# WAFC.net
KiCad netlist of a schematic drawn in Altium Designer
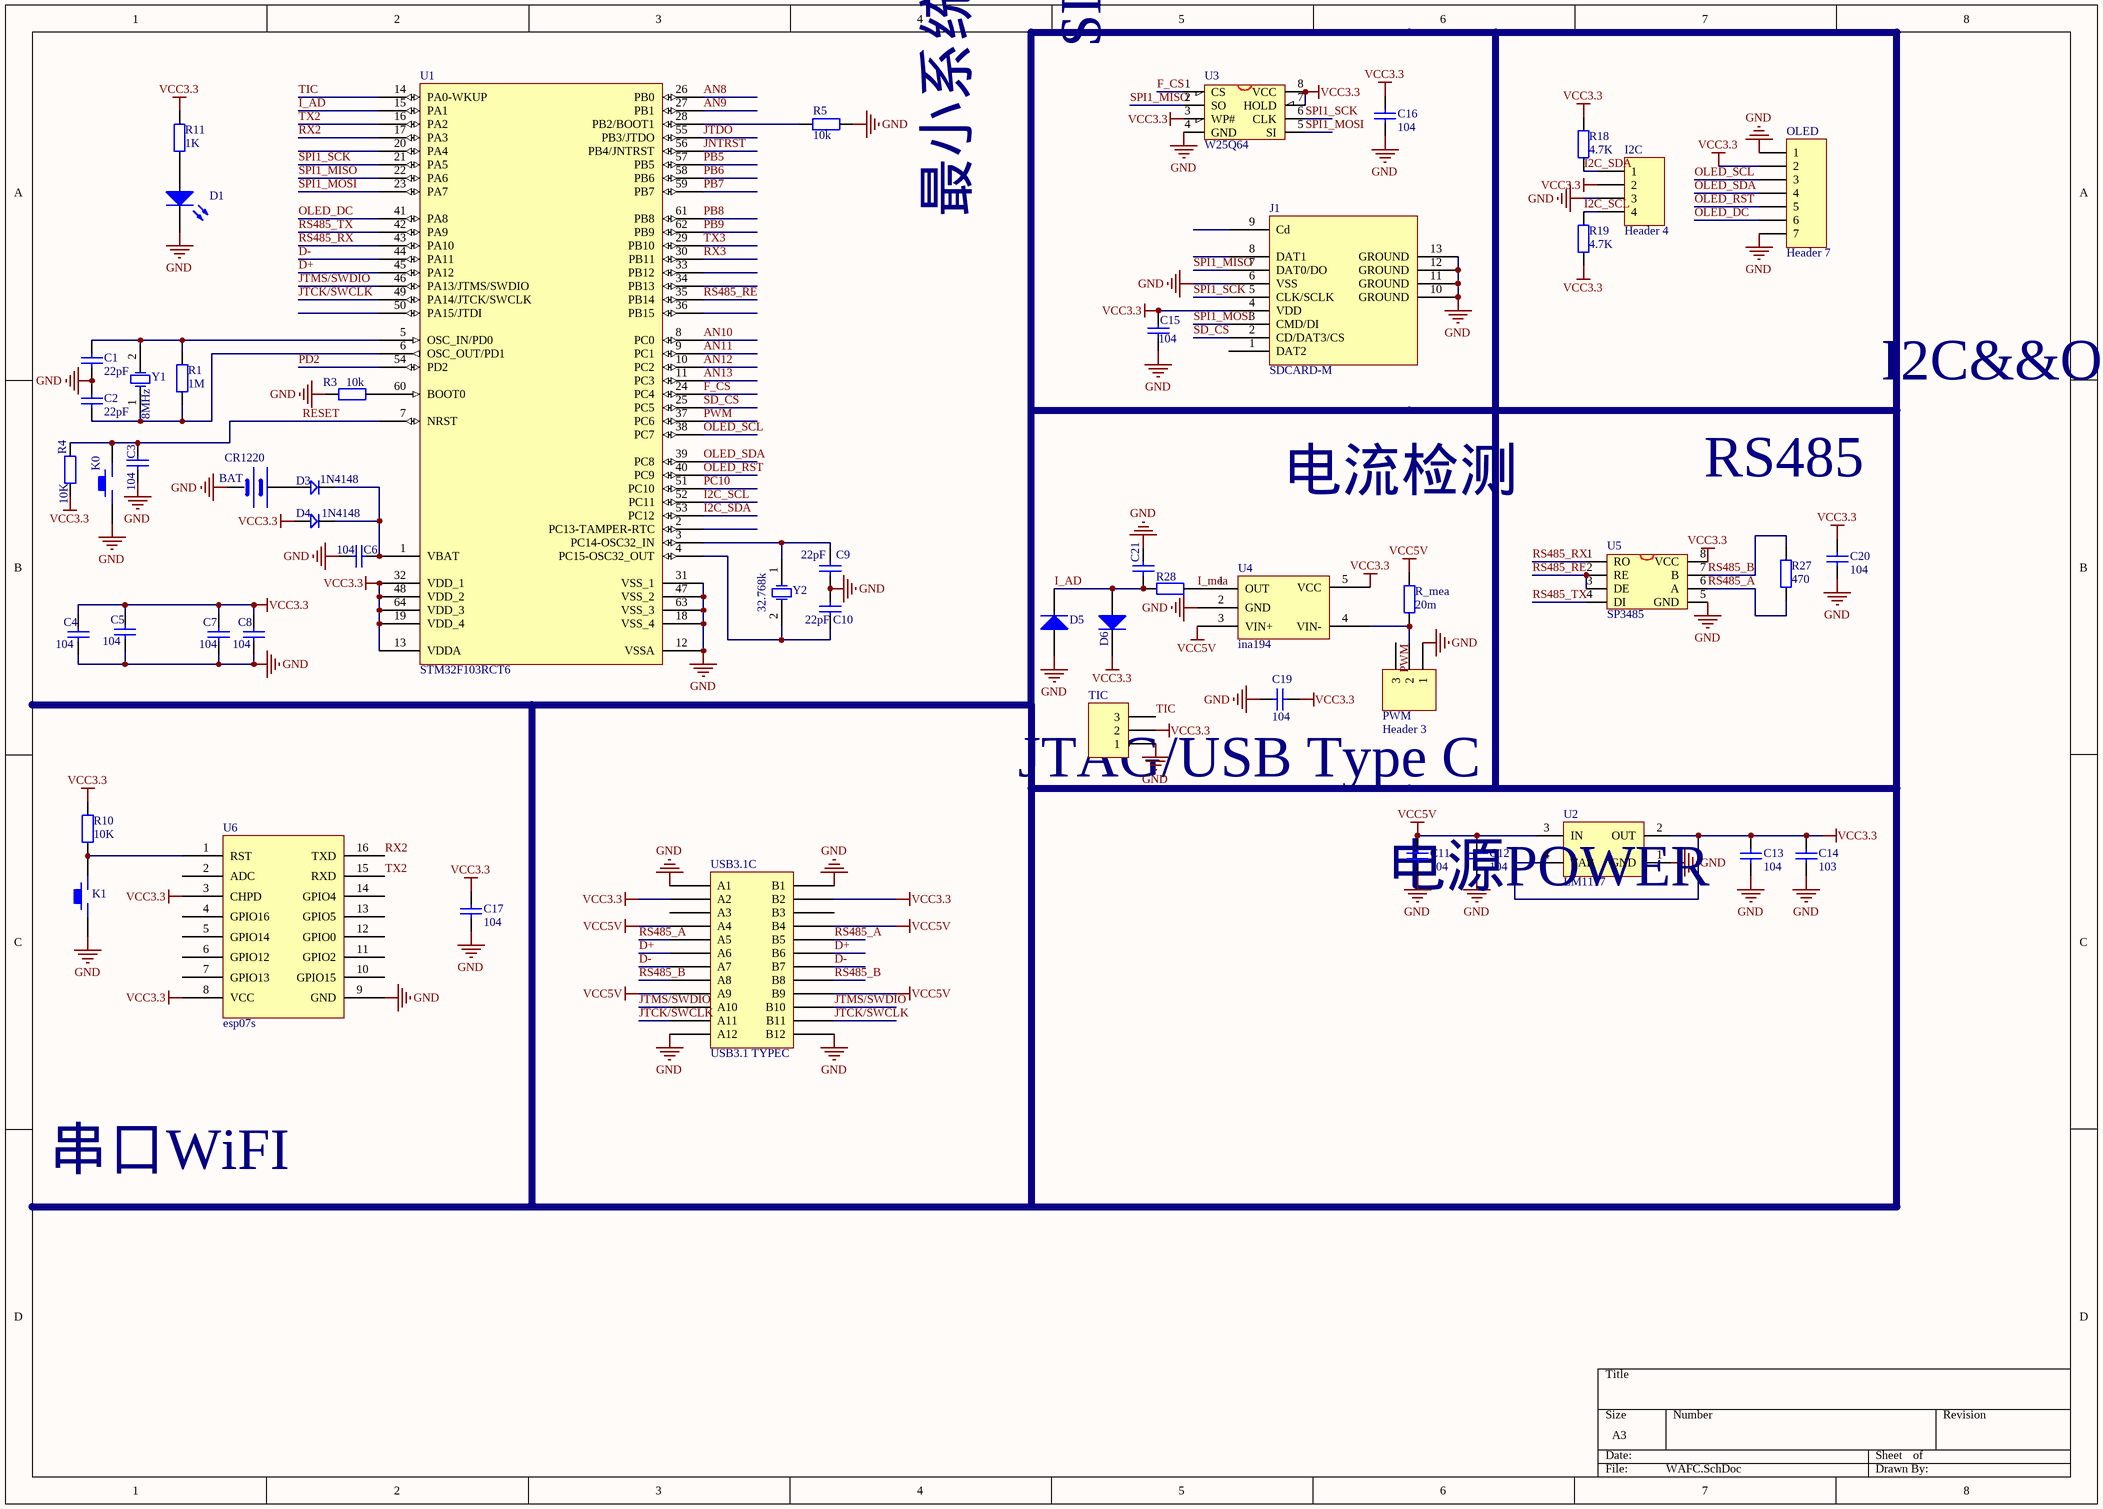
[diagram p0: WAFC.SchDoc]

(export (version "E")
  (design (tool "Eeschema 10.0.6"))
  (components
    (comp (ref "BAT") (value "CR1220") (footprint "BATM") (libsource (lib "WARSHIP") (part "BAT")))
    (comp (ref "C1")
      (value "22pF")
      (footprint "0603")
      (description "Capacitor")
      (fields (field (name "Comment") "Cap") (field (name "PUBLISHER") "Altium Limited"))
      (libsource (lib "Miscellaneous Devices") (part "Cap"))
    )
    (comp (ref "C2")
      (value "22pF")
      (footprint "0603")
      (description "Capacitor")
      (fields (field (name "Comment") "Cap") (field (name "PUBLISHER") "Altium Limited"))
      (libsource (lib "Miscellaneous Devices") (part "Cap"))
    )
    (comp (ref "C3")
      (value "104")
      (footprint "0603")
      (description "Capacitor")
      (fields (field (name "Comment") "Cap") (field (name "PUBLISHER") "Altium Limited"))
      (libsource (lib "Miscellaneous Devices") (part "Cap"))
    )
    (comp (ref "C4")
      (value "104")
      (footprint "0603")
      (description "Capacitor")
      (fields (field (name "Comment") "Cap") (field (name "PUBLISHER") "Altium Limited"))
      (libsource (lib "Miscellaneous Devices") (part "Cap"))
    )
    (comp (ref "C5")
      (value "104")
      (footprint "0603")
      (description "Capacitor")
      (fields (field (name "Comment") "Cap") (field (name "PUBLISHER") "Altium Limited"))
      (libsource (lib "Miscellaneous Devices") (part "Cap"))
    )
    (comp (ref "C6")
      (value "104")
      (footprint "0603")
      (description "Capacitor")
      (fields (field (name "Comment") "Cap") (field (name "PUBLISHER") "Altium Limited"))
      (libsource (lib "Miscellaneous Devices") (part "Cap"))
    )
    (comp (ref "C7")
      (value "104")
      (footprint "0603")
      (description "Capacitor")
      (fields (field (name "Comment") "Cap") (field (name "PUBLISHER") "Altium Limited"))
      (libsource (lib "Miscellaneous Devices") (part "Cap"))
    )
    (comp (ref "C8")
      (value "104")
      (footprint "0603")
      (description "Capacitor")
      (fields (field (name "Comment") "Cap") (field (name "PUBLISHER") "Altium Limited"))
      (libsource (lib "Miscellaneous Devices") (part "Cap"))
    )
    (comp (ref "C9")
      (value "22pF")
      (footprint "0603")
      (description "Capacitor")
      (fields (field (name "Comment") "Cap") (field (name "PUBLISHER") "Altium Limited"))
      (libsource (lib "Miscellaneous Devices") (part "Cap"))
    )
    (comp (ref "C10")
      (value "22pF")
      (footprint "0603")
      (description "Capacitor")
      (fields (field (name "Comment") "Cap") (field (name "PUBLISHER") "Altium Limited"))
      (libsource (lib "Miscellaneous Devices") (part "Cap"))
    )
    (comp (ref "C11")
      (value "104")
      (footprint "0603")
      (description "Capacitor")
      (fields (field (name "Comment") "Cap") (field (name "PUBLISHER") "Altium Limited"))
      (libsource (lib "Miscellaneous Devices") (part "Cap"))
    )
    (comp (ref "C12")
      (value "104")
      (footprint "0603")
      (description "Capacitor")
      (fields (field (name "Comment") "Cap") (field (name "PUBLISHER") "Altium Limited"))
      (libsource (lib "Miscellaneous Devices") (part "Cap"))
    )
    (comp (ref "C13")
      (value "104")
      (footprint "0603")
      (description "Capacitor")
      (fields (field (name "Comment") "Cap") (field (name "PUBLISHER") "Altium Limited"))
      (libsource (lib "Miscellaneous Devices") (part "Cap"))
    )
    (comp (ref "C14")
      (value "103")
      (footprint "0603")
      (description "Capacitor")
      (fields (field (name "Comment") "Cap") (field (name "PUBLISHER") "Altium Limited"))
      (libsource (lib "Miscellaneous Devices") (part "Cap"))
    )
    (comp (ref "C15")
      (value "104")
      (footprint "0603")
      (description "Capacitor")
      (fields (field (name "Comment") "Cap") (field (name "PUBLISHER") "Altium Limited"))
      (libsource (lib "Miscellaneous Devices") (part "Cap"))
    )
    (comp (ref "C16")
      (value "104")
      (footprint "0603")
      (description "Capacitor")
      (fields (field (name "Comment") "Cap") (field (name "PUBLISHER") "Altium Limited"))
      (libsource (lib "Miscellaneous Devices") (part "Cap"))
    )
    (comp (ref "C17")
      (value "104")
      (footprint "0603")
      (description "Capacitor")
      (fields (field (name "Comment") "Cap") (field (name "PUBLISHER") "Altium Limited"))
      (libsource (lib "Miscellaneous Devices") (part "Cap"))
    )
    (comp (ref "C19")
      (value "104")
      (footprint "0603")
      (description "Capacitor")
      (fields (field (name "Comment") "Cap") (field (name "PUBLISHER") "Altium Limited"))
      (libsource (lib "Miscellaneous Devices") (part "Cap"))
    )
    (comp (ref "C20")
      (value "104")
      (footprint "0603")
      (description "Capacitor")
      (fields (field (name "Comment") "Cap") (field (name "PUBLISHER") "Altium Limited"))
      (libsource (lib "Miscellaneous Devices") (part "Cap"))
    )
    (comp (ref "C21")
      (value "Cap")
      (footprint "0603")
      (description "Capacitor")
      (fields (field (name "PUBLISHER") "Altium Limited"))
      (libsource (lib "Miscellaneous Devices") (part "Cap"))
    )
    (comp (ref "D1")
      (value "LED2")
      (footprint "0603")
      (description "Typical RED, GREEN, YELLOW, AMBER GaAs LED")
      (fields (field (name "PUBLISHER") "Altium Limited"))
      (libsource (lib "Miscellaneous Devices") (part "LED2"))
    )
    (comp (ref "D3") (value "1N4148") (footprint "DIODE_SOP") (libsource (lib "WARSHIP") (part "D")))
    (comp (ref "D4") (value "1N4148") (footprint "DIODE_SOP") (libsource (lib "WARSHIP") (part "D")))
    (comp (ref "D5")
      (value "SS14")
      (footprint "IN5819")
      (description "1 Amp General Purpose Rectifier")
      (fields (field (name "PUBLISHER") "Altium Limited"))
      (libsource (lib "Miscellaneous Devices") (part "Diode 1N4007"))
    )
    (comp (ref "D6")
      (value "SS14")
      (footprint "IN5819")
      (description "1 Amp General Purpose Rectifier")
      (fields (field (name "PUBLISHER") "Altium Limited"))
      (libsource (lib "Miscellaneous Devices") (part "Diode 1N4007"))
    )
    (comp (ref "I2C")
      (value "Header 4")
      (footprint "4P")
      (description "Header, 4-Pin")
      (fields (field (name "PUBLISHER") "Altium Limited"))
      (libsource (lib "Miscellaneous Connectors") (part "Header 4"))
    )
    (comp (ref "J1")
      (value "SDCARD-M")
      (footprint "SDCARD-M")
      (description "TF卡槽")
      (libsource (lib "MYLIB") (part "SDCARD-M"))
    )
    (comp (ref "K0") (value "K1") (footprint "sop2") (libsource (lib "MYLIB") (part "KEY")))
    (comp (ref "K1") (value "K3") (footprint "sop2") (libsource (lib "MYLIB") (part "KEY")))
    (comp (ref "OLED")
      (value "Header 7")
      (footprint "HDR1X7")
      (description "Header, 7-Pin")
      (fields (field (name "PUBLISHER") "Altium Limited"))
      (libsource (lib "Miscellaneous Connectors") (part "Header 7"))
    )
    (comp (ref "PWM")
      (value "Header 3")
      (footprint "HDR1X3")
      (description "Header, 3-Pin")
      (fields (field (name "PUBLISHER") "Altium Limited"))
      (libsource (lib "") (part "Header 3_1"))
    )
    (comp (ref "R1")
      (value "1M")
      (footprint "0603")
      (description "Resistor")
      (fields (field (name "Comment") "Res2") (field (name "PUBLISHER") "Altium Limited"))
      (libsource (lib "") (part "Res2_1"))
    )
    (comp (ref "R3")
      (value "10k")
      (footprint "0603")
      (description "Resistor")
      (fields (field (name "Comment") "Res2") (field (name "PUBLISHER") "Altium Limited"))
      (libsource (lib "") (part "Res2_2"))
    )
    (comp (ref "R4")
      (value "10K")
      (footprint "0603")
      (description "Resistor")
      (fields (field (name "Comment") "Res2") (field (name "PUBLISHER") "Altium Limited"))
      (libsource (lib "") (part "Res2_1"))
    )
    (comp (ref "R5")
      (value "10k")
      (footprint "0603")
      (description "Resistor")
      (fields (field (name "Comment") "Res2") (field (name "PUBLISHER") "Altium Limited"))
      (libsource (lib "") (part "Res2_2"))
    )
    (comp (ref "R10")
      (value "10K")
      (footprint "0603")
      (description "Resistor")
      (fields (field (name "Comment") "Res2") (field (name "PUBLISHER") "Altium Limited"))
      (libsource (lib "Miscellaneous Devices") (part "Res2"))
    )
    (comp (ref "R11")
      (value "1K")
      (footprint "0603")
      (description "Resistor")
      (fields (field (name "Comment") "Res2") (field (name "PUBLISHER") "Altium Limited"))
      (libsource (lib "") (part "Res2_1"))
    )
    (comp (ref "R18")
      (value "4.7K")
      (footprint "0603")
      (description "Resistor")
      (fields (field (name "Comment") "Res2") (field (name "PUBLISHER") "Altium Limited"))
      (libsource (lib "Miscellaneous Devices") (part "Res2"))
    )
    (comp (ref "R19")
      (value "4.7K")
      (footprint "0603")
      (description "Resistor")
      (fields (field (name "Comment") "Res2") (field (name "PUBLISHER") "Altium Limited"))
      (libsource (lib "Miscellaneous Devices") (part "Res2"))
    )
    (comp (ref "R27")
      (value "470")
      (footprint "0603")
      (description "Resistor")
      (fields (field (name "Comment") "Res2") (field (name "PUBLISHER") "Altium Limited"))
      (libsource (lib "Miscellaneous Devices") (part "Res2"))
    )
    (comp (ref "R28")
      (value "Res2")
      (footprint "0603")
      (description "Resistor")
      (fields (field (name "PUBLISHER") "Altium Limited"))
      (libsource (lib "") (part "Res2_3"))
    )
    (comp (ref "R_mea")
      (value "20m")
      (footprint "0805")
      (description "Resistor")
      (fields (field (name "Comment") "Res2") (field (name "PUBLISHER") "Altium Limited"))
      (libsource (lib "") (part "Res2_1"))
    )
    (comp (ref "TIC")
      (value "Header 3")
      (footprint "HDR1X3")
      (description "Header, 3-Pin")
      (fields (field (name "PUBLISHER") "Altium Limited"))
      (libsource (lib "Miscellaneous Connectors") (part "Header 3"))
    )
    (comp (ref "U1")
      (value "STM32F103RCT6")
      (footprint "LQFP64")
      (description "STM32 ARM-based 32-bit MCU with 128 Kbytes Flash, 64-pin LQFP, Industrial Temperature")
      (fields (field (name "PUBLISHER") "Altium Limited"))
      (libsource (lib "MYLIB") (part "STM32F103RBT6"))
    )
    (comp (ref "U2")
      (value "LM1117")
      (footprint "MP04A_N")
      (description "800mA LDO")
      (fields
        (field (name "PARTNUMBER") "LM1117IMP-5.0")
        (field (name "MANUFACTURER") "National Semiconductor")
        (field (name "PUBLISHER") "Altium Limited")
      )
      (libsource (lib "MYLIB") (part "LM1117"))
    )
    (comp (ref "U3")
      (value "W25Q64")
      (footprint "SOIC-8")
      (description "W25X16;SST25VF016;MX25L1605")
      (libsource (lib "WARSHIP") (part "W25X16"))
    )
    (comp (ref "U4") (value "ina194") (footprint "ina194") (libsource (lib "MYLIB") (part "ina194")))
    (comp (ref "U5") (value "SP3485") (footprint "SOP-8") (libsource (lib "WARSHIP") (part "MAX3485")))
    (comp (ref "U6") (value "esp07s") (footprint "ESP07S") (libsource (lib "MYLIB") (part "esp07s")))
    (comp (ref "USB3.1C")
      (value "USB3.1 TYPEC")
      (footprint "MicroUSB TypeC 3.1 - duplicate")
      (libsource (lib "MYLIB") (part "USB3.1 TYPEc"))
    )
    (comp (ref "Y1")
      (value "8MHz")
      (footprint "XTAL_US")
      (description "Crystal Oscillator")
      (fields (field (name "PUBLISHER") "Altium Limited"))
      (libsource (lib "WARSHIP") (part "XTAL"))
    )
    (comp (ref "Y2")
      (value "32.768k")
      (footprint "XTAL32768")
      (description "Crystal Oscillator")
      (fields (field (name "PUBLISHER") "Altium Limited"))
      (libsource (lib "Miscellaneous Devices") (part "XTAL"))
    )
  )
  (nets
    (net (code "1") (name "/AN8") (class "Default")
      (node (ref "U1") (pin "26") (pinfunction "PB0_26") (pintype "bidirectional"))
    )
    (net (code "2") (name "/AN9") (class "Default")
      (node (ref "U1") (pin "27") (pinfunction "PB1_27") (pintype "bidirectional"))
    )
    (net (code "3") (name "/AN10") (class "Default")
      (node (ref "U1") (pin "8") (pinfunction "PC0_8") (pintype "bidirectional"))
    )
    (net (code "4") (name "/AN11") (class "Default")
      (node (ref "U1") (pin "9") (pinfunction "PC1_9") (pintype "bidirectional"))
    )
    (net (code "5") (name "/AN12") (class "Default")
      (node (ref "U1") (pin "10") (pinfunction "PC2_10") (pintype "bidirectional"))
    )
    (net (code "6") (name "/AN13") (class "Default")
      (node (ref "U1") (pin "11") (pinfunction "PC3_11") (pintype "bidirectional"))
    )
    (net (code "7") (name "/D+") (class "Default")
      (node (ref "U1") (pin "45") (pinfunction "PA12_45") (pintype "bidirectional"))
      (node (ref "USB3.1C") (pin "19") (pinfunction "B6_19") (pintype "passive"))
      (node (ref "USB3.1C") (pin "6") (pinfunction "A6_6") (pintype "passive"))
    )
    (net (code "8") (name "/D-") (class "Default")
      (node (ref "U1") (pin "44") (pinfunction "PA11_44") (pintype "bidirectional"))
      (node (ref "USB3.1C") (pin "18") (pinfunction "B7_18") (pintype "passive"))
      (node (ref "USB3.1C") (pin "7") (pinfunction "A7_7") (pintype "passive"))
    )
    (net (code "9") (name "/F_CS") (class "Default")
      (node (ref "U1") (pin "24") (pinfunction "PC4_24") (pintype "bidirectional"))
      (node (ref "U3") (pin "1") (pinfunction "CS_1") (pintype "passive"))
    )
    (net (code "10") (name "/I2C_SCL") (class "Default")
      (node (ref "I2C") (pin "4") (pinfunction "4_4") (pintype "passive"))
      (node (ref "R19") (pin "1") (pinfunction "1_1") (pintype "passive"))
      (node (ref "U1") (pin "52") (pinfunction "PC11_52") (pintype "bidirectional"))
    )
    (net (code "11") (name "/I2C_SDA") (class "Default")
      (node (ref "I2C") (pin "1") (pinfunction "1_1") (pintype "passive"))
      (node (ref "R18") (pin "2") (pinfunction "2_2") (pintype "passive"))
      (node (ref "U1") (pin "53") (pinfunction "PC12_53") (pintype "bidirectional"))
    )
    (net (code "12") (name "/I_AD") (class "Default")
      (node (ref "C21") (pin "1") (pinfunction "1_1") (pintype "passive"))
      (node (ref "D5") (pin "2") (pinfunction "K_2") (pintype "passive"))
      (node (ref "D6") (pin "1") (pinfunction "A_1") (pintype "passive"))
      (node (ref "R28") (pin "1") (pinfunction "1_1") (pintype "passive"))
      (node (ref "U1") (pin "15") (pinfunction "PA1_15") (pintype "bidirectional"))
    )
    (net (code "13") (name "/I_mea") (class "Default")
      (node (ref "R28") (pin "2") (pinfunction "2_2") (pintype "passive"))
      (node (ref "U4") (pin "1") (pinfunction "OUT_1") (pintype "passive"))
    )
    (net (code "14") (name "/JNTRST") (class "Default")
      (node (ref "U1") (pin "56") (pinfunction "PB4/JNTRST_56") (pintype "bidirectional"))
    )
    (net (code "15") (name "/JTCK{slash}SWCLK") (class "Default")
      (node (ref "U1") (pin "49") (pinfunction "PA14/JTCK/SWCLK_49") (pintype "bidirectional"))
      (node (ref "USB3.1C") (pin "11") (pinfunction "A11_11") (pintype "passive"))
      (node (ref "USB3.1C") (pin "14") (pinfunction "B11_14") (pintype "passive"))
    )
    (net (code "16") (name "/JTDO") (class "Default")
      (node (ref "U1") (pin "55") (pinfunction "PB3/JTDO_55") (pintype "bidirectional"))
    )
    (net (code "17") (name "/JTMS{slash}SWDIO") (class "Default")
      (node (ref "U1") (pin "46") (pinfunction "PA13/JTMS/SWDIO_46") (pintype "bidirectional"))
      (node (ref "USB3.1C") (pin "10") (pinfunction "A10_10") (pintype "passive"))
      (node (ref "USB3.1C") (pin "15") (pinfunction "B10_15") (pintype "passive"))
    )
    (net (code "18") (name "/OLED_DC") (class "Default")
      (node (ref "OLED") (pin "6") (pinfunction "6_6") (pintype "passive"))
      (node (ref "U1") (pin "41") (pinfunction "PA8_41") (pintype "bidirectional"))
    )
    (net (code "19") (name "/OLED_RST") (class "Default")
      (node (ref "OLED") (pin "5") (pinfunction "5_5") (pintype "passive"))
      (node (ref "U1") (pin "40") (pinfunction "PC9_40") (pintype "bidirectional"))
    )
    (net (code "20") (name "/OLED_SCL") (class "Default")
      (node (ref "OLED") (pin "3") (pinfunction "3_3") (pintype "passive"))
      (node (ref "U1") (pin "38") (pinfunction "PC7_38") (pintype "bidirectional"))
    )
    (net (code "21") (name "/OLED_SDA") (class "Default")
      (node (ref "OLED") (pin "4") (pinfunction "4_4") (pintype "passive"))
      (node (ref "U1") (pin "39") (pinfunction "PC8_39") (pintype "bidirectional"))
    )
    (net (code "22") (name "/PB5") (class "Default")
      (node (ref "U1") (pin "57") (pinfunction "PB5_57") (pintype "bidirectional"))
    )
    (net (code "23") (name "/PB6") (class "Default")
      (node (ref "U1") (pin "58") (pinfunction "PB6_58") (pintype "bidirectional"))
    )
    (net (code "24") (name "/PB7") (class "Default")
      (node (ref "U1") (pin "59") (pinfunction "PB7_59") (pintype "bidirectional"))
    )
    (net (code "25") (name "/PB8") (class "Default")
      (node (ref "U1") (pin "61") (pinfunction "PB8_61") (pintype "bidirectional"))
    )
    (net (code "26") (name "/PB9") (class "Default")
      (node (ref "U1") (pin "62") (pinfunction "PB9_62") (pintype "bidirectional"))
    )
    (net (code "27") (name "/PC10") (class "Default")
      (node (ref "U1") (pin "51") (pinfunction "PC10_51") (pintype "bidirectional"))
    )
    (net (code "28") (name "/PD2") (class "Default")
      (node (ref "U1") (pin "54") (pinfunction "PD2_54") (pintype "bidirectional"))
    )
    (net (code "29") (name "/PWM") (class "Default")
      (node (ref "PWM") (pin "3") (pinfunction "3_3") (pintype "passive"))
      (node (ref "U1") (pin "37") (pinfunction "PC6_37") (pintype "bidirectional"))
    )
    (net (code "30") (name "/RESET") (class "Default")
      (node (ref "C3") (pin "2") (pinfunction "2_2") (pintype "passive"))
      (node (ref "K0") (pin "2") (pinfunction "2_2") (pintype "passive"))
      (node (ref "R4") (pin "2") (pinfunction "2_2") (pintype "passive"))
      (node (ref "U1") (pin "7") (pinfunction "NRST_7") (pintype "bidirectional"))
    )
    (net (code "31") (name "/RS485_A") (class "Default")
      (node (ref "R27") (pin "2") (pinfunction "2_2") (pintype "passive"))
      (node (ref "U5") (pin "6") (pinfunction "A_6") (pintype "passive"))
      (node (ref "USB3.1C") (pin "20") (pinfunction "B5_20") (pintype "passive"))
      (node (ref "USB3.1C") (pin "5") (pinfunction "A5_5") (pintype "passive"))
    )
    (net (code "32") (name "/RS485_B") (class "Default")
      (node (ref "R27") (pin "1") (pinfunction "1_1") (pintype "passive"))
      (node (ref "U5") (pin "7") (pinfunction "B_7") (pintype "passive"))
      (node (ref "USB3.1C") (pin "17") (pinfunction "B8_17") (pintype "passive"))
      (node (ref "USB3.1C") (pin "8") (pinfunction "A8_8") (pintype "passive"))
    )
    (net (code "33") (name "/RS485_RE") (class "Default")
      (node (ref "U1") (pin "35") (pinfunction "PB14_35") (pintype "bidirectional"))
      (node (ref "U5") (pin "2") (pinfunction "RE_2") (pintype "passive"))
      (node (ref "U5") (pin "3") (pinfunction "DE_3") (pintype "passive"))
    )
    (net (code "34") (name "/RS485_RX") (class "Default")
      (node (ref "U1") (pin "43") (pinfunction "PA10_43") (pintype "bidirectional"))
      (node (ref "U5") (pin "1") (pinfunction "RO_1") (pintype "passive"))
    )
    (net (code "35") (name "/RS485_TX") (class "Default")
      (node (ref "U1") (pin "42") (pinfunction "PA9_42") (pintype "bidirectional"))
      (node (ref "U5") (pin "4") (pinfunction "DI_4") (pintype "passive"))
    )
    (net (code "36") (name "/RX2") (class "Default")
      (node (ref "U1") (pin "17") (pinfunction "PA3_17") (pintype "bidirectional"))
      (node (ref "U6") (pin "16") (pinfunction "TXD_16") (pintype "passive"))
    )
    (net (code "37") (name "/RX3") (class "Default")
      (node (ref "U1") (pin "30") (pinfunction "PB11_30") (pintype "bidirectional"))
    )
    (net (code "38") (name "/SD_CS") (class "Default")
      (node (ref "J1") (pin "2") (pinfunction "CD/DAT3/CS_2") (pintype "passive"))
      (node (ref "U1") (pin "25") (pinfunction "PC5_25") (pintype "bidirectional"))
    )
    (net (code "39") (name "/SPI1_MISO") (class "Default")
      (node (ref "J1") (pin "7") (pinfunction "DAT0/DO_7") (pintype "passive"))
      (node (ref "U1") (pin "22") (pinfunction "PA6_22") (pintype "bidirectional"))
      (node (ref "U3") (pin "2") (pinfunction "SO_2") (pintype "passive"))
    )
    (net (code "40") (name "/SPI1_MOSI") (class "Default")
      (node (ref "J1") (pin "3") (pinfunction "CMD/DI_3") (pintype "passive"))
      (node (ref "U1") (pin "23") (pinfunction "PA7_23") (pintype "bidirectional"))
      (node (ref "U3") (pin "5") (pinfunction "SI_5") (pintype "passive"))
    )
    (net (code "41") (name "/SPI1_SCK") (class "Default")
      (node (ref "J1") (pin "5") (pinfunction "CLK/SCLK_5") (pintype "passive"))
      (node (ref "U1") (pin "21") (pinfunction "PA5_21") (pintype "bidirectional"))
      (node (ref "U3") (pin "6") (pinfunction "CLK_6") (pintype "passive"))
    )
    (net (code "42") (name "/TIC") (class "Default")
      (node (ref "TIC") (pin "3") (pinfunction "3_3") (pintype "passive"))
      (node (ref "U1") (pin "14") (pinfunction "PA0-WKUP_14") (pintype "bidirectional"))
    )
    (net (code "43") (name "/TX2") (class "Default")
      (node (ref "U1") (pin "16") (pinfunction "PA2_16") (pintype "bidirectional"))
      (node (ref "U6") (pin "15") (pinfunction "RXD_15") (pintype "passive"))
    )
    (net (code "44") (name "/TX3") (class "Default")
      (node (ref "U1") (pin "29") (pinfunction "PB10_29") (pintype "bidirectional"))
    )
    (net (code "45") (name "GND") (class "Default")
      (node (ref "BAT") (pin "2") (pinfunction "GND_2") (pintype "passive"))
      (node (ref "C1") (pin "1") (pinfunction "1_1") (pintype "passive"))
      (node (ref "C10") (pin "1") (pinfunction "1_1") (pintype "passive"))
      (node (ref "C11") (pin "1") (pinfunction "1_1") (pintype "passive"))
      (node (ref "C12") (pin "1") (pinfunction "1_1") (pintype "passive"))
      (node (ref "C13") (pin "1") (pinfunction "1_1") (pintype "passive"))
      (node (ref "C14") (pin "1") (pinfunction "1_1") (pintype "passive"))
      (node (ref "C15") (pin "1") (pinfunction "1_1") (pintype "passive"))
      (node (ref "C16") (pin "1") (pinfunction "1_1") (pintype "passive"))
      (node (ref "C17") (pin "1") (pinfunction "1_1") (pintype "passive"))
      (node (ref "C19") (pin "1") (pinfunction "1_1") (pintype "passive"))
      (node (ref "C2") (pin "2") (pinfunction "2_2") (pintype "passive"))
      (node (ref "C20") (pin "1") (pinfunction "1_1") (pintype "passive"))
      (node (ref "C21") (pin "2") (pinfunction "2_2") (pintype "passive"))
      (node (ref "C3") (pin "1") (pinfunction "1_1") (pintype "passive"))
      (node (ref "C4") (pin "2") (pinfunction "2_2") (pintype "passive"))
      (node (ref "C5") (pin "2") (pinfunction "2_2") (pintype "passive"))
      (node (ref "C6") (pin "2") (pinfunction "2_2") (pintype "passive"))
      (node (ref "C7") (pin "2") (pinfunction "2_2") (pintype "passive"))
      (node (ref "C8") (pin "2") (pinfunction "2_2") (pintype "passive"))
      (node (ref "C9") (pin "2") (pinfunction "2_2") (pintype "passive"))
      (node (ref "D1") (pin "2") (pinfunction "K_2") (pintype "passive"))
      (node (ref "D5") (pin "1") (pinfunction "A_1") (pintype "passive"))
      (node (ref "I2C") (pin "3") (pinfunction "3_3") (pintype "passive"))
      (node (ref "J1") (pin "10") (pinfunction "GROUND_10") (pintype "passive"))
      (node (ref "J1") (pin "11") (pinfunction "GROUND_11") (pintype "passive"))
      (node (ref "J1") (pin "12") (pinfunction "GROUND_12") (pintype "passive"))
      (node (ref "J1") (pin "13") (pinfunction "GROUND_13") (pintype "passive"))
      (node (ref "J1") (pin "6") (pinfunction "VSS_6") (pintype "passive"))
      (node (ref "K0") (pin "1") (pinfunction "1_1") (pintype "passive"))
      (node (ref "K1") (pin "1") (pinfunction "1_1") (pintype "passive"))
      (node (ref "OLED") (pin "1") (pinfunction "1_1") (pintype "passive"))
      (node (ref "OLED") (pin "7") (pinfunction "7_7") (pintype "passive"))
      (node (ref "PWM") (pin "1") (pinfunction "1_1") (pintype "passive"))
      (node (ref "R3") (pin "2") (pinfunction "2_2") (pintype "passive"))
      (node (ref "R5") (pin "1") (pinfunction "1_1") (pintype "passive"))
      (node (ref "TIC") (pin "1") (pinfunction "1_1") (pintype "passive"))
      (node (ref "U1") (pin "12") (pinfunction "VSSA_12") (pintype "power_in"))
      (node (ref "U1") (pin "18") (pinfunction "VSS_4_18") (pintype "power_in"))
      (node (ref "U1") (pin "31") (pinfunction "VSS_1_31") (pintype "power_in"))
      (node (ref "U1") (pin "47") (pinfunction "VSS_2_47") (pintype "power_in"))
      (node (ref "U1") (pin "63") (pinfunction "VSS_3_63") (pintype "power_in"))
      (node (ref "U2") (pin "1") (pinfunction "GND_1") (pintype "power_in"))
      (node (ref "U3") (pin "4") (pinfunction "GND_4") (pintype "passive"))
      (node (ref "U4") (pin "2") (pinfunction "GND_2") (pintype "passive"))
      (node (ref "U5") (pin "5") (pinfunction "GND_5") (pintype "passive"))
      (node (ref "U6") (pin "9") (pinfunction "GND_9") (pintype "passive"))
      (node (ref "USB3.1C") (pin "1") (pinfunction "A1_1") (pintype "passive"))
      (node (ref "USB3.1C") (pin "12") (pinfunction "A12_12") (pintype "passive"))
      (node (ref "USB3.1C") (pin "13") (pinfunction "B12_13") (pintype "passive"))
      (node (ref "USB3.1C") (pin "24") (pinfunction "B1_24") (pintype "passive"))
    )
    (net (code "46") (name "Net-(BAT-VCC)") (class "Default")
      (node (ref "BAT") (pin "1") (pinfunction "VCC_1") (pintype "passive"))
      (node (ref "D3") (pin "1") (pintype "passive"))
    )
    (net (code "47") (name "Net-(D1-A)") (class "Default")
      (node (ref "D1") (pin "1") (pinfunction "A_1") (pintype "passive"))
      (node (ref "R11") (pin "1") (pinfunction "1_1") (pintype "passive"))
    )
    (net (code "48") (name "Net-(U1-BOOT0)") (class "Default")
      (node (ref "R3") (pin "1") (pinfunction "1_1") (pintype "passive"))
      (node (ref "U1") (pin "60") (pinfunction "BOOT0_60") (pintype "input"))
    )
    (net (code "49") (name "Net-(U1-OSC_IN{slash}PD0)") (class "Default")
      (node (ref "C1") (pin "2") (pinfunction "2_2") (pintype "passive"))
      (node (ref "R1") (pin "2") (pinfunction "2_2") (pintype "passive"))
      (node (ref "U1") (pin "5") (pinfunction "OSC_IN/PD0_5") (pintype "input"))
      (node (ref "Y1") (pin "2") (pinfunction "OSC2_2") (pintype "passive"))
    )
    (net (code "50") (name "Net-(U1-OSC_OUT{slash}PD1)") (class "Default")
      (node (ref "C2") (pin "1") (pinfunction "1_1") (pintype "passive"))
      (node (ref "R1") (pin "1") (pinfunction "1_1") (pintype "passive"))
      (node (ref "U1") (pin "6") (pinfunction "OSC_OUT/PD1_6") (pintype "output"))
      (node (ref "Y1") (pin "1") (pinfunction "OSC1_1") (pintype "passive"))
    )
    (net (code "51") (name "Net-(U1-PB2{slash}BOOT1)") (class "Default")
      (node (ref "R5") (pin "2") (pinfunction "2_2") (pintype "passive"))
      (node (ref "U1") (pin "28") (pinfunction "PB2/BOOT1_28") (pintype "bidirectional"))
    )
    (net (code "52") (name "Net-(U1-PC14-OSC32_IN)") (class "Default")
      (node (ref "C9") (pin "1") (pinfunction "1_1") (pintype "passive"))
      (node (ref "U1") (pin "3") (pinfunction "PC14-OSC32_IN_3") (pintype "bidirectional"))
      (node (ref "Y2") (pin "1") (pinfunction "OSC1_1") (pintype "passive"))
    )
    (net (code "53") (name "Net-(U1-PC15-OSC32_OUT)") (class "Default")
      (node (ref "C10") (pin "2") (pinfunction "2_2") (pintype "passive"))
      (node (ref "U1") (pin "4") (pinfunction "PC15-OSC32_OUT_4") (pintype "bidirectional"))
      (node (ref "Y2") (pin "2") (pinfunction "OSC2_2") (pintype "passive"))
    )
    (net (code "54") (name "Net-(U1-VBAT)") (class "Default")
      (node (ref "C6") (pin "1") (pinfunction "1_1") (pintype "passive"))
      (node (ref "D3") (pin "2") (pintype "passive"))
      (node (ref "D4") (pin "2") (pintype "passive"))
      (node (ref "U1") (pin "1") (pinfunction "VBAT_1") (pintype "power_in"))
    )
    (net (code "55") (name "Net-(U4-VIN-)") (class "Default")
      (node (ref "PWM") (pin "2") (pinfunction "2_2") (pintype "passive"))
      (node (ref "R_mea") (pin "1") (pinfunction "1_1") (pintype "passive"))
      (node (ref "U4") (pin "4") (pinfunction "VIN-_4") (pintype "passive"))
    )
    (net (code "56") (name "Net-(U6-RST)") (class "Default")
      (node (ref "K1") (pin "2") (pinfunction "2_2") (pintype "passive"))
      (node (ref "R10") (pin "2") (pinfunction "2_2") (pintype "passive"))
      (node (ref "U6") (pin "1") (pinfunction "RST_1") (pintype "passive"))
    )
    (net (code "57") (name "VCC3.3") (class "Default")
      (node (ref "C13") (pin "2") (pinfunction "2_2") (pintype "passive"))
      (node (ref "C14") (pin "2") (pinfunction "2_2") (pintype "passive"))
      (node (ref "C15") (pin "2") (pinfunction "2_2") (pintype "passive"))
      (node (ref "C16") (pin "2") (pinfunction "2_2") (pintype "passive"))
      (node (ref "C17") (pin "2") (pinfunction "2_2") (pintype "passive"))
      (node (ref "C19") (pin "2") (pinfunction "2_2") (pintype "passive"))
      (node (ref "C20") (pin "2") (pinfunction "2_2") (pintype "passive"))
      (node (ref "C4") (pin "1") (pinfunction "1_1") (pintype "passive"))
      (node (ref "C5") (pin "1") (pinfunction "1_1") (pintype "passive"))
      (node (ref "C7") (pin "1") (pinfunction "1_1") (pintype "passive"))
      (node (ref "C8") (pin "1") (pinfunction "1_1") (pintype "passive"))
      (node (ref "D4") (pin "1") (pintype "passive"))
      (node (ref "D6") (pin "2") (pinfunction "K_2") (pintype "passive"))
      (node (ref "I2C") (pin "2") (pinfunction "2_2") (pintype "passive"))
      (node (ref "J1") (pin "4") (pinfunction "VDD_4") (pintype "passive"))
      (node (ref "OLED") (pin "2") (pinfunction "2_2") (pintype "passive"))
      (node (ref "R10") (pin "1") (pinfunction "1_1") (pintype "passive"))
      (node (ref "R11") (pin "2") (pinfunction "2_2") (pintype "passive"))
      (node (ref "R18") (pin "1") (pinfunction "1_1") (pintype "passive"))
      (node (ref "R19") (pin "2") (pinfunction "2_2") (pintype "passive"))
      (node (ref "R4") (pin "1") (pinfunction "1_1") (pintype "passive"))
      (node (ref "TIC") (pin "2") (pinfunction "2_2") (pintype "passive"))
      (node (ref "U1") (pin "13") (pinfunction "VDDA_13") (pintype "power_in"))
      (node (ref "U1") (pin "19") (pinfunction "VDD_4_19") (pintype "power_in"))
      (node (ref "U1") (pin "32") (pinfunction "VDD_1_32") (pintype "power_in"))
      (node (ref "U1") (pin "48") (pinfunction "VDD_2_48") (pintype "power_in"))
      (node (ref "U1") (pin "64") (pinfunction "VDD_3_64") (pintype "power_in"))
      (node (ref "U2") (pin "2") (pinfunction "OUT_2") (pintype "power_in"))
      (node (ref "U2") (pin "4") (pinfunction "TAB_4") (pintype "power_in"))
      (node (ref "U3") (pin "3") (pinfunction "WP#_3") (pintype "passive"))
      (node (ref "U3") (pin "7") (pinfunction "HOLD_7") (pintype "passive"))
      (node (ref "U3") (pin "8") (pinfunction "VCC_8") (pintype "passive"))
      (node (ref "U4") (pin "5") (pinfunction "VCC_5") (pintype "passive"))
      (node (ref "U5") (pin "8") (pinfunction "VCC_8") (pintype "passive"))
      (node (ref "U6") (pin "3") (pinfunction "CHPD_3") (pintype "passive"))
      (node (ref "U6") (pin "8") (pinfunction "VCC_8") (pintype "passive"))
      (node (ref "USB3.1C") (pin "2") (pinfunction "A2_2") (pintype "passive"))
      (node (ref "USB3.1C") (pin "23") (pinfunction "B2_23") (pintype "passive"))
    )
    (net (code "58") (name "VCC5V") (class "Default")
      (node (ref "C11") (pin "2") (pinfunction "2_2") (pintype "passive"))
      (node (ref "C12") (pin "2") (pinfunction "2_2") (pintype "passive"))
      (node (ref "R_mea") (pin "2") (pinfunction "2_2") (pintype "passive"))
      (node (ref "U2") (pin "3") (pinfunction "IN_3") (pintype "power_in"))
      (node (ref "U4") (pin "3") (pinfunction "VIN+_3") (pintype "passive"))
      (node (ref "USB3.1C") (pin "16") (pinfunction "B9_16") (pintype "passive"))
      (node (ref "USB3.1C") (pin "21") (pinfunction "B4_21") (pintype "passive"))
      (node (ref "USB3.1C") (pin "4") (pinfunction "A4_4") (pintype "passive"))
      (node (ref "USB3.1C") (pin "9") (pinfunction "A9_9") (pintype "passive"))
    )
    (net (code "59") (name "unconnected-(J1-Cd-Pad9)") (class "Default")
      (node (ref "J1") (pin "9") (pinfunction "Cd_9") (pintype "passive"))
    )
    (net (code "60") (name "unconnected-(J1-DAT1-Pad8)") (class "Default")
      (node (ref "J1") (pin "8") (pinfunction "DAT1_8") (pintype "passive"))
    )
    (net (code "61") (name "unconnected-(J1-DAT2-Pad1)") (class "Default")
      (node (ref "J1") (pin "1") (pinfunction "DAT2_1") (pintype "passive"))
    )
    (net (code "62") (name "unconnected-(U1-PA4-Pad20)") (class "Default")
      (node (ref "U1") (pin "20") (pinfunction "PA4_20") (pintype "bidirectional"))
    )
    (net (code "63") (name "unconnected-(U1-PA15{slash}JTDI-Pad50)") (class "Default")
      (node (ref "U1") (pin "50") (pinfunction "PA15/JTDI_50") (pintype "bidirectional"))
    )
    (net (code "64") (name "unconnected-(U1-PB12-Pad33)") (class "Default")
      (node (ref "U1") (pin "33") (pinfunction "PB12_33") (pintype "bidirectional"))
    )
    (net (code "65") (name "unconnected-(U1-PB13-Pad34)") (class "Default")
      (node (ref "U1") (pin "34") (pinfunction "PB13_34") (pintype "bidirectional"))
    )
    (net (code "66") (name "unconnected-(U1-PB15-Pad36)") (class "Default")
      (node (ref "U1") (pin "36") (pinfunction "PB15_36") (pintype "bidirectional"))
    )
    (net (code "67") (name "unconnected-(U1-PC13-TAMPER-RTC-Pad2)") (class "Default")
      (node (ref "U1") (pin "2") (pinfunction "PC13-TAMPER-RTC_2") (pintype "bidirectional"))
    )
    (net (code "68") (name "unconnected-(U6-ADC-Pad2)") (class "Default")
      (node (ref "U6") (pin "2") (pinfunction "ADC_2") (pintype "passive"))
    )
    (net (code "69") (name "unconnected-(U6-GPIO0-Pad12)") (class "Default")
      (node (ref "U6") (pin "12") (pinfunction "GPIO0_12") (pintype "passive"))
    )
    (net (code "70") (name "unconnected-(U6-GPIO2-Pad11)") (class "Default")
      (node (ref "U6") (pin "11") (pinfunction "GPIO2_11") (pintype "passive"))
    )
    (net (code "71") (name "unconnected-(U6-GPIO4-Pad14)") (class "Default")
      (node (ref "U6") (pin "14") (pinfunction "GPIO4_14") (pintype "passive"))
    )
    (net (code "72") (name "unconnected-(U6-GPIO5-Pad13)") (class "Default")
      (node (ref "U6") (pin "13") (pinfunction "GPIO5_13") (pintype "passive"))
    )
    (net (code "73") (name "unconnected-(U6-GPIO12-Pad6)") (class "Default")
      (node (ref "U6") (pin "6") (pinfunction "GPIO12_6") (pintype "passive"))
    )
    (net (code "74") (name "unconnected-(U6-GPIO13-Pad7)") (class "Default")
      (node (ref "U6") (pin "7") (pinfunction "GPIO13_7") (pintype "passive"))
    )
    (net (code "75") (name "unconnected-(U6-GPIO14-Pad5)") (class "Default")
      (node (ref "U6") (pin "5") (pinfunction "GPIO14_5") (pintype "passive"))
    )
    (net (code "76") (name "unconnected-(U6-GPIO15-Pad10)") (class "Default")
      (node (ref "U6") (pin "10") (pinfunction "GPIO15_10") (pintype "passive"))
    )
    (net (code "77") (name "unconnected-(U6-GPIO16-Pad4)") (class "Default")
      (node (ref "U6") (pin "4") (pinfunction "GPIO16_4") (pintype "passive"))
    )
    (net (code "78") (name "unconnected-(USB3.1C-A3-Pad3)") (class "Default")
      (node (ref "USB3.1C") (pin "3") (pinfunction "A3_3") (pintype "passive"))
    )
    (net (code "79") (name "unconnected-(USB3.1C-B3-Pad22)") (class "Default")
      (node (ref "USB3.1C") (pin "22") (pinfunction "B3_22") (pintype "passive"))
    )
  )
)
